# Sheet1.net
KiCad netlist of a schematic drawn in Altium Designer
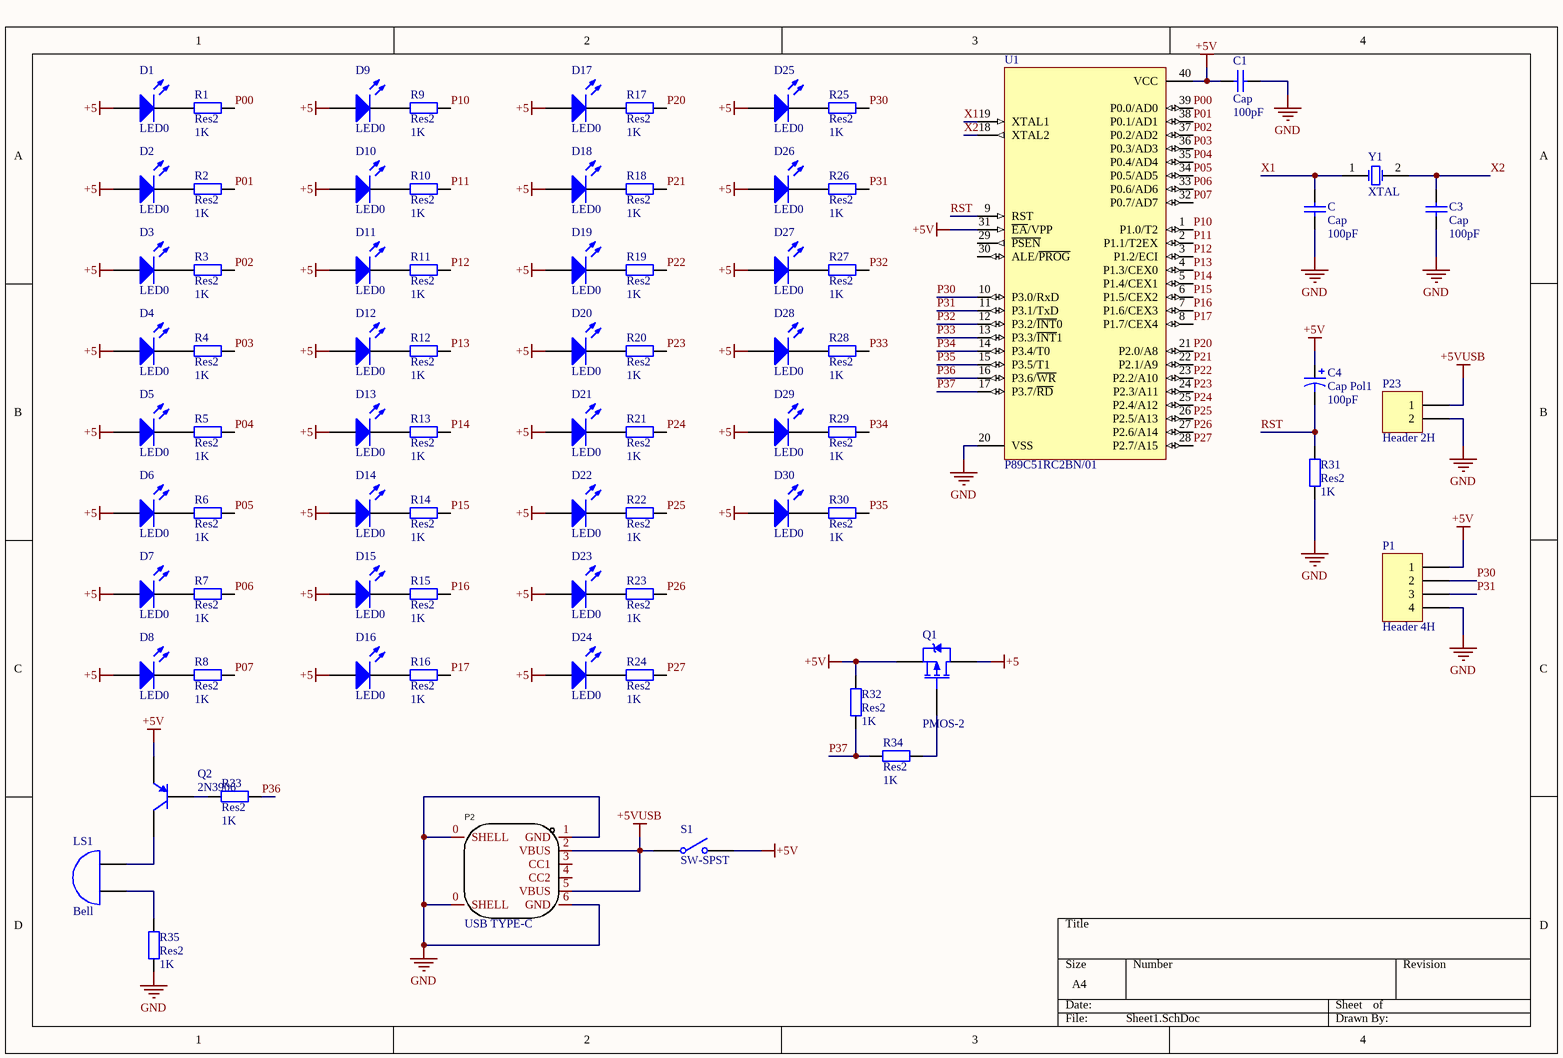
[diagram p0: Sheet1.SchDoc]

(export (version "E")
  (design (tool "Eeschema 10.0.6"))
  (components
    (comp (ref "C")
      (value "Cap")
      (footprint "C-0.1")
      (description "Capacitor")
      (fields (field (name "ALTIUM_VALUE") "100pF") (field (name "PUBLISHER") "Altium Limited"))
      (libsource (lib "Miscellaneous Devices") (part "Cap"))
    )
    (comp (ref "C1")
      (value "Cap")
      (footprint "C-0.1")
      (description "Capacitor")
      (fields (field (name "ALTIUM_VALUE") "100pF") (field (name "PUBLISHER") "Altium Limited"))
      (libsource (lib "Miscellaneous Devices") (part "Cap"))
    )
    (comp (ref "C3")
      (value "Cap")
      (footprint "C-0.1")
      (description "Capacitor")
      (fields (field (name "ALTIUM_VALUE") "100pF") (field (name "PUBLISHER") "Altium Limited"))
      (libsource (lib "Miscellaneous Devices") (part "Cap"))
    )
    (comp (ref "C4")
      (value "Cap Pol1")
      (footprint "CD-0.2T")
      (description "Polarized Capacitor (Radial)")
      (fields (field (name "ALTIUM_VALUE") "100pF") (field (name "PUBLISHER") "Altium Limited"))
      (libsource (lib "Miscellaneous Devices") (part "Cap Pol1"))
    )
    (comp (ref "D1")
      (value "LED0")
      (footprint "led5")
      (description "Typical INFRARED GaAs LED")
      (fields (field (name "PUBLISHER") "Altium Limited"))
      (libsource (lib "Miscellaneous Devices") (part "LED0"))
    )
    (comp (ref "D2")
      (value "LED0")
      (footprint "led5")
      (description "Typical INFRARED GaAs LED")
      (fields (field (name "PUBLISHER") "Altium Limited"))
      (libsource (lib "Miscellaneous Devices") (part "LED0"))
    )
    (comp (ref "D3")
      (value "LED0")
      (footprint "led5")
      (description "Typical INFRARED GaAs LED")
      (fields (field (name "PUBLISHER") "Altium Limited"))
      (libsource (lib "Miscellaneous Devices") (part "LED0"))
    )
    (comp (ref "D4")
      (value "LED0")
      (footprint "led5")
      (description "Typical INFRARED GaAs LED")
      (fields (field (name "PUBLISHER") "Altium Limited"))
      (libsource (lib "Miscellaneous Devices") (part "LED0"))
    )
    (comp (ref "D5")
      (value "LED0")
      (footprint "led5")
      (description "Typical INFRARED GaAs LED")
      (fields (field (name "PUBLISHER") "Altium Limited"))
      (libsource (lib "Miscellaneous Devices") (part "LED0"))
    )
    (comp (ref "D6")
      (value "LED0")
      (footprint "led5")
      (description "Typical INFRARED GaAs LED")
      (fields (field (name "PUBLISHER") "Altium Limited"))
      (libsource (lib "Miscellaneous Devices") (part "LED0"))
    )
    (comp (ref "D7")
      (value "LED0")
      (footprint "led5")
      (description "Typical INFRARED GaAs LED")
      (fields (field (name "PUBLISHER") "Altium Limited"))
      (libsource (lib "Miscellaneous Devices") (part "LED0"))
    )
    (comp (ref "D8")
      (value "LED0")
      (footprint "led5")
      (description "Typical INFRARED GaAs LED")
      (fields (field (name "PUBLISHER") "Altium Limited"))
      (libsource (lib "Miscellaneous Devices") (part "LED0"))
    )
    (comp (ref "D9")
      (value "LED0")
      (footprint "led5")
      (description "Typical INFRARED GaAs LED")
      (fields (field (name "PUBLISHER") "Altium Limited"))
      (libsource (lib "Miscellaneous Devices") (part "LED0"))
    )
    (comp (ref "D10")
      (value "LED0")
      (footprint "led5")
      (description "Typical INFRARED GaAs LED")
      (fields (field (name "PUBLISHER") "Altium Limited"))
      (libsource (lib "Miscellaneous Devices") (part "LED0"))
    )
    (comp (ref "D11")
      (value "LED0")
      (footprint "led5")
      (description "Typical INFRARED GaAs LED")
      (fields (field (name "PUBLISHER") "Altium Limited"))
      (libsource (lib "Miscellaneous Devices") (part "LED0"))
    )
    (comp (ref "D12")
      (value "LED0")
      (footprint "led5")
      (description "Typical INFRARED GaAs LED")
      (fields (field (name "PUBLISHER") "Altium Limited"))
      (libsource (lib "Miscellaneous Devices") (part "LED0"))
    )
    (comp (ref "D13")
      (value "LED0")
      (footprint "led5")
      (description "Typical INFRARED GaAs LED")
      (fields (field (name "PUBLISHER") "Altium Limited"))
      (libsource (lib "Miscellaneous Devices") (part "LED0"))
    )
    (comp (ref "D14")
      (value "LED0")
      (footprint "led5")
      (description "Typical INFRARED GaAs LED")
      (fields (field (name "PUBLISHER") "Altium Limited"))
      (libsource (lib "Miscellaneous Devices") (part "LED0"))
    )
    (comp (ref "D15")
      (value "LED0")
      (footprint "led5")
      (description "Typical INFRARED GaAs LED")
      (fields (field (name "PUBLISHER") "Altium Limited"))
      (libsource (lib "Miscellaneous Devices") (part "LED0"))
    )
    (comp (ref "D16")
      (value "LED0")
      (footprint "led5")
      (description "Typical INFRARED GaAs LED")
      (fields (field (name "PUBLISHER") "Altium Limited"))
      (libsource (lib "Miscellaneous Devices") (part "LED0"))
    )
    (comp (ref "D17")
      (value "LED0")
      (footprint "led5")
      (description "Typical INFRARED GaAs LED")
      (fields (field (name "PUBLISHER") "Altium Limited"))
      (libsource (lib "Miscellaneous Devices") (part "LED0"))
    )
    (comp (ref "D18")
      (value "LED0")
      (footprint "led5")
      (description "Typical INFRARED GaAs LED")
      (fields (field (name "PUBLISHER") "Altium Limited"))
      (libsource (lib "Miscellaneous Devices") (part "LED0"))
    )
    (comp (ref "D19")
      (value "LED0")
      (footprint "led5")
      (description "Typical INFRARED GaAs LED")
      (fields (field (name "PUBLISHER") "Altium Limited"))
      (libsource (lib "Miscellaneous Devices") (part "LED0"))
    )
    (comp (ref "D20")
      (value "LED0")
      (footprint "led5")
      (description "Typical INFRARED GaAs LED")
      (fields (field (name "PUBLISHER") "Altium Limited"))
      (libsource (lib "Miscellaneous Devices") (part "LED0"))
    )
    (comp (ref "D21")
      (value "LED0")
      (footprint "led5")
      (description "Typical INFRARED GaAs LED")
      (fields (field (name "PUBLISHER") "Altium Limited"))
      (libsource (lib "Miscellaneous Devices") (part "LED0"))
    )
    (comp (ref "D22")
      (value "LED0")
      (footprint "led5")
      (description "Typical INFRARED GaAs LED")
      (fields (field (name "PUBLISHER") "Altium Limited"))
      (libsource (lib "Miscellaneous Devices") (part "LED0"))
    )
    (comp (ref "D23")
      (value "LED0")
      (footprint "led5")
      (description "Typical INFRARED GaAs LED")
      (fields (field (name "PUBLISHER") "Altium Limited"))
      (libsource (lib "Miscellaneous Devices") (part "LED0"))
    )
    (comp (ref "D24")
      (value "LED0")
      (footprint "led5")
      (description "Typical INFRARED GaAs LED")
      (fields (field (name "PUBLISHER") "Altium Limited"))
      (libsource (lib "Miscellaneous Devices") (part "LED0"))
    )
    (comp (ref "D25")
      (value "LED0")
      (footprint "led5")
      (description "Typical INFRARED GaAs LED")
      (fields (field (name "PUBLISHER") "Altium Limited"))
      (libsource (lib "Miscellaneous Devices") (part "LED0"))
    )
    (comp (ref "D26")
      (value "LED0")
      (footprint "led5")
      (description "Typical INFRARED GaAs LED")
      (fields (field (name "PUBLISHER") "Altium Limited"))
      (libsource (lib "Miscellaneous Devices") (part "LED0"))
    )
    (comp (ref "D27")
      (value "LED0")
      (footprint "led5")
      (description "Typical INFRARED GaAs LED")
      (fields (field (name "PUBLISHER") "Altium Limited"))
      (libsource (lib "Miscellaneous Devices") (part "LED0"))
    )
    (comp (ref "D28")
      (value "LED0")
      (footprint "led5")
      (description "Typical INFRARED GaAs LED")
      (fields (field (name "PUBLISHER") "Altium Limited"))
      (libsource (lib "Miscellaneous Devices") (part "LED0"))
    )
    (comp (ref "D29")
      (value "LED0")
      (footprint "led5")
      (description "Typical INFRARED GaAs LED")
      (fields (field (name "PUBLISHER") "Altium Limited"))
      (libsource (lib "Miscellaneous Devices") (part "LED0"))
    )
    (comp (ref "D30")
      (value "LED0")
      (footprint "led5")
      (description "Typical INFRARED GaAs LED")
      (fields (field (name "PUBLISHER") "Altium Limited"))
      (libsource (lib "Miscellaneous Devices") (part "LED0"))
    )
    (comp (ref "LS1")
      (value "Bell")
      (footprint "PIN2")
      (description "Electrical Bell")
      (fields (field (name "PUBLISHER") "Altium Limited"))
      (libsource (lib "Miscellaneous Devices") (part "Bell"))
    )
    (comp (ref "P1")
      (value "Header 4H")
      (footprint "SIP4")
      (description "Header, 4-Pin, Right Angle")
      (fields (field (name "PUBLISHER") "Altium Limited"))
      (libsource (lib "Miscellaneous Connectors") (part "Header 4H"))
    )
    (comp (ref "P2")
      (value "USB TYPE-C")
      (footprint "USBTYPEC6")
      (fields (field (name "MANUFACTURER PART") "TYPE-C 6P CB1.6(073)"))
      (libsource (lib "EPL Scblib") (part "USB TYPE-C 6P"))
    )
    (comp (ref "P23")
      (value "Header 2H")
      (footprint "HDR1X2H")
      (description "Header, 2-Pin, Right Angle")
      (fields (field (name "PUBLISHER") "Altium Limited"))
      (libsource (lib "Miscellaneous Connectors") (part "Header 2H"))
    )
    (comp (ref "Q1")
      (value "PMOS-2")
      (footprint "sot23")
      (description "P-Channel Power MOSFET")
      (fields (field (name "PUBLISHER") "Altium Limited"))
      (libsource (lib "EPL Scblib") (part "AO3401"))
    )
    (comp (ref "Q2")
      (value "2N3906")
      (footprint "TO-92A")
      (description "PNP General Purpose Amplifier")
      (fields (field (name "PUBLISHER") "Altium Limited"))
      (libsource (lib "Miscellaneous Devices") (part "2N3906"))
    )
    (comp (ref "R1")
      (value "Res2")
      (footprint "R-0.3")
      (description "Resistor")
      (fields (field (name "ALTIUM_VALUE") "1K") (field (name "PUBLISHER") "Altium Limited"))
      (libsource (lib "Miscellaneous Devices") (part "Res2"))
    )
    (comp (ref "R2")
      (value "Res2")
      (footprint "R-0.3")
      (description "Resistor")
      (fields (field (name "ALTIUM_VALUE") "1K") (field (name "PUBLISHER") "Altium Limited"))
      (libsource (lib "Miscellaneous Devices") (part "Res2"))
    )
    (comp (ref "R3")
      (value "Res2")
      (footprint "R-0.3")
      (description "Resistor")
      (fields (field (name "ALTIUM_VALUE") "1K") (field (name "PUBLISHER") "Altium Limited"))
      (libsource (lib "Miscellaneous Devices") (part "Res2"))
    )
    (comp (ref "R4")
      (value "Res2")
      (footprint "R-0.3")
      (description "Resistor")
      (fields (field (name "ALTIUM_VALUE") "1K") (field (name "PUBLISHER") "Altium Limited"))
      (libsource (lib "Miscellaneous Devices") (part "Res2"))
    )
    (comp (ref "R5")
      (value "Res2")
      (footprint "R-0.3")
      (description "Resistor")
      (fields (field (name "ALTIUM_VALUE") "1K") (field (name "PUBLISHER") "Altium Limited"))
      (libsource (lib "Miscellaneous Devices") (part "Res2"))
    )
    (comp (ref "R6")
      (value "Res2")
      (footprint "R-0.3")
      (description "Resistor")
      (fields (field (name "ALTIUM_VALUE") "1K") (field (name "PUBLISHER") "Altium Limited"))
      (libsource (lib "Miscellaneous Devices") (part "Res2"))
    )
    (comp (ref "R7")
      (value "Res2")
      (footprint "R-0.3")
      (description "Resistor")
      (fields (field (name "ALTIUM_VALUE") "1K") (field (name "PUBLISHER") "Altium Limited"))
      (libsource (lib "Miscellaneous Devices") (part "Res2"))
    )
    (comp (ref "R8")
      (value "Res2")
      (footprint "R-0.3")
      (description "Resistor")
      (fields (field (name "ALTIUM_VALUE") "1K") (field (name "PUBLISHER") "Altium Limited"))
      (libsource (lib "Miscellaneous Devices") (part "Res2"))
    )
    (comp (ref "R9")
      (value "Res2")
      (footprint "R-0.3")
      (description "Resistor")
      (fields (field (name "ALTIUM_VALUE") "1K") (field (name "PUBLISHER") "Altium Limited"))
      (libsource (lib "Miscellaneous Devices") (part "Res2"))
    )
    (comp (ref "R10")
      (value "Res2")
      (footprint "R-0.3")
      (description "Resistor")
      (fields (field (name "ALTIUM_VALUE") "1K") (field (name "PUBLISHER") "Altium Limited"))
      (libsource (lib "Miscellaneous Devices") (part "Res2"))
    )
    (comp (ref "R11")
      (value "Res2")
      (footprint "R-0.3")
      (description "Resistor")
      (fields (field (name "ALTIUM_VALUE") "1K") (field (name "PUBLISHER") "Altium Limited"))
      (libsource (lib "Miscellaneous Devices") (part "Res2"))
    )
    (comp (ref "R12")
      (value "Res2")
      (footprint "R-0.3")
      (description "Resistor")
      (fields (field (name "ALTIUM_VALUE") "1K") (field (name "PUBLISHER") "Altium Limited"))
      (libsource (lib "Miscellaneous Devices") (part "Res2"))
    )
    (comp (ref "R13")
      (value "Res2")
      (footprint "R-0.3")
      (description "Resistor")
      (fields (field (name "ALTIUM_VALUE") "1K") (field (name "PUBLISHER") "Altium Limited"))
      (libsource (lib "Miscellaneous Devices") (part "Res2"))
    )
    (comp (ref "R14")
      (value "Res2")
      (footprint "R-0.3")
      (description "Resistor")
      (fields (field (name "ALTIUM_VALUE") "1K") (field (name "PUBLISHER") "Altium Limited"))
      (libsource (lib "Miscellaneous Devices") (part "Res2"))
    )
    (comp (ref "R15")
      (value "Res2")
      (footprint "R-0.3")
      (description "Resistor")
      (fields (field (name "ALTIUM_VALUE") "1K") (field (name "PUBLISHER") "Altium Limited"))
      (libsource (lib "Miscellaneous Devices") (part "Res2"))
    )
    (comp (ref "R16")
      (value "Res2")
      (footprint "R-0.3")
      (description "Resistor")
      (fields (field (name "ALTIUM_VALUE") "1K") (field (name "PUBLISHER") "Altium Limited"))
      (libsource (lib "Miscellaneous Devices") (part "Res2"))
    )
    (comp (ref "R17")
      (value "Res2")
      (footprint "R-0.3")
      (description "Resistor")
      (fields (field (name "ALTIUM_VALUE") "1K") (field (name "PUBLISHER") "Altium Limited"))
      (libsource (lib "Miscellaneous Devices") (part "Res2"))
    )
    (comp (ref "R18")
      (value "Res2")
      (footprint "R-0.3")
      (description "Resistor")
      (fields (field (name "ALTIUM_VALUE") "1K") (field (name "PUBLISHER") "Altium Limited"))
      (libsource (lib "Miscellaneous Devices") (part "Res2"))
    )
    (comp (ref "R19")
      (value "Res2")
      (footprint "R-0.3")
      (description "Resistor")
      (fields (field (name "ALTIUM_VALUE") "1K") (field (name "PUBLISHER") "Altium Limited"))
      (libsource (lib "Miscellaneous Devices") (part "Res2"))
    )
    (comp (ref "R20")
      (value "Res2")
      (footprint "R-0.3")
      (description "Resistor")
      (fields (field (name "ALTIUM_VALUE") "1K") (field (name "PUBLISHER") "Altium Limited"))
      (libsource (lib "Miscellaneous Devices") (part "Res2"))
    )
    (comp (ref "R21")
      (value "Res2")
      (footprint "R-0.3")
      (description "Resistor")
      (fields (field (name "ALTIUM_VALUE") "1K") (field (name "PUBLISHER") "Altium Limited"))
      (libsource (lib "Miscellaneous Devices") (part "Res2"))
    )
    (comp (ref "R22")
      (value "Res2")
      (footprint "R-0.3")
      (description "Resistor")
      (fields (field (name "ALTIUM_VALUE") "1K") (field (name "PUBLISHER") "Altium Limited"))
      (libsource (lib "Miscellaneous Devices") (part "Res2"))
    )
    (comp (ref "R23")
      (value "Res2")
      (footprint "R-0.3")
      (description "Resistor")
      (fields (field (name "ALTIUM_VALUE") "1K") (field (name "PUBLISHER") "Altium Limited"))
      (libsource (lib "Miscellaneous Devices") (part "Res2"))
    )
    (comp (ref "R24")
      (value "Res2")
      (footprint "R-0.3")
      (description "Resistor")
      (fields (field (name "ALTIUM_VALUE") "1K") (field (name "PUBLISHER") "Altium Limited"))
      (libsource (lib "Miscellaneous Devices") (part "Res2"))
    )
    (comp (ref "R25")
      (value "Res2")
      (footprint "R-0.3")
      (description "Resistor")
      (fields (field (name "ALTIUM_VALUE") "1K") (field (name "PUBLISHER") "Altium Limited"))
      (libsource (lib "Miscellaneous Devices") (part "Res2"))
    )
    (comp (ref "R26")
      (value "Res2")
      (footprint "R-0.3")
      (description "Resistor")
      (fields (field (name "ALTIUM_VALUE") "1K") (field (name "PUBLISHER") "Altium Limited"))
      (libsource (lib "Miscellaneous Devices") (part "Res2"))
    )
    (comp (ref "R27")
      (value "Res2")
      (footprint "R-0.3")
      (description "Resistor")
      (fields (field (name "ALTIUM_VALUE") "1K") (field (name "PUBLISHER") "Altium Limited"))
      (libsource (lib "Miscellaneous Devices") (part "Res2"))
    )
    (comp (ref "R28")
      (value "Res2")
      (footprint "R-0.3")
      (description "Resistor")
      (fields (field (name "ALTIUM_VALUE") "1K") (field (name "PUBLISHER") "Altium Limited"))
      (libsource (lib "Miscellaneous Devices") (part "Res2"))
    )
    (comp (ref "R29")
      (value "Res2")
      (footprint "R-0.3")
      (description "Resistor")
      (fields (field (name "ALTIUM_VALUE") "1K") (field (name "PUBLISHER") "Altium Limited"))
      (libsource (lib "Miscellaneous Devices") (part "Res2"))
    )
    (comp (ref "R30")
      (value "Res2")
      (footprint "R-0.3")
      (description "Resistor")
      (fields (field (name "ALTIUM_VALUE") "1K") (field (name "PUBLISHER") "Altium Limited"))
      (libsource (lib "Miscellaneous Devices") (part "Res2"))
    )
    (comp (ref "R31")
      (value "Res2")
      (footprint "R-0.3")
      (description "Resistor")
      (fields (field (name "ALTIUM_VALUE") "1K") (field (name "PUBLISHER") "Altium Limited"))
      (libsource (lib "") (part "Res2_1"))
    )
    (comp (ref "R32")
      (value "Res2")
      (footprint "R-0.3")
      (description "Resistor")
      (fields (field (name "ALTIUM_VALUE") "1K") (field (name "PUBLISHER") "Altium Limited"))
      (libsource (lib "") (part "Res2_1"))
    )
    (comp (ref "R33")
      (value "Res2")
      (footprint "R-0.3")
      (description "Resistor")
      (fields (field (name "ALTIUM_VALUE") "1K") (field (name "PUBLISHER") "Altium Limited"))
      (libsource (lib "") (part "Res2_2"))
    )
    (comp (ref "R34")
      (value "Res2")
      (footprint "R-0.3")
      (description "Resistor")
      (fields (field (name "ALTIUM_VALUE") "1K") (field (name "PUBLISHER") "Altium Limited"))
      (libsource (lib "") (part "Res2_2"))
    )
    (comp (ref "R35")
      (value "Res2")
      (footprint "R-0.3")
      (description "Resistor")
      (fields (field (name "ALTIUM_VALUE") "1K") (field (name "PUBLISHER") "Altium Limited"))
      (libsource (lib "") (part "Res2_1"))
    )
    (comp (ref "S1")
      (value "SW-SPST")
      (footprint "onoff")
      (description "Single-Pole, Single-Throw Switch")
      (fields (field (name "PUBLISHER") "Altium Limited"))
      (libsource (lib "Miscellaneous Devices") (part "SW-SPST"))
    )
    (comp (ref "U1")
      (value "P89C51RC2BN/01")
      (footprint "DIP40")
      (description "80C51 8-Bit Flash Microcontroller Family, 32 kB ISP/IAP Flash with 512 B RAM.")
      (fields (field (name "PUBLISHER") "Altium Limited"))
      (libsource (lib "Philips Microcontroller 8-Bit") (part "P89C51RC2BN/01"))
    )
    (comp (ref "Y1")
      (value "XTAL")
      (footprint "jz")
      (description "Crystal Oscillator")
      (fields (field (name "PUBLISHER") "Altium Limited"))
      (libsource (lib "Miscellaneous Devices") (part "XTAL"))
    )
  )
  (nets
    (net (code "1") (name "+5") (class "Default")
      (node (ref "D1") (pin "1") (pinfunction "A_1") (pintype "passive"))
      (node (ref "D10") (pin "1") (pinfunction "A_1") (pintype "passive"))
      (node (ref "D11") (pin "1") (pinfunction "A_1") (pintype "passive"))
      (node (ref "D12") (pin "1") (pinfunction "A_1") (pintype "passive"))
      (node (ref "D13") (pin "1") (pinfunction "A_1") (pintype "passive"))
      (node (ref "D14") (pin "1") (pinfunction "A_1") (pintype "passive"))
      (node (ref "D15") (pin "1") (pinfunction "A_1") (pintype "passive"))
      (node (ref "D16") (pin "1") (pinfunction "A_1") (pintype "passive"))
      (node (ref "D17") (pin "1") (pinfunction "A_1") (pintype "passive"))
      (node (ref "D18") (pin "1") (pinfunction "A_1") (pintype "passive"))
      (node (ref "D19") (pin "1") (pinfunction "A_1") (pintype "passive"))
      (node (ref "D2") (pin "1") (pinfunction "A_1") (pintype "passive"))
      (node (ref "D20") (pin "1") (pinfunction "A_1") (pintype "passive"))
      (node (ref "D21") (pin "1") (pinfunction "A_1") (pintype "passive"))
      (node (ref "D22") (pin "1") (pinfunction "A_1") (pintype "passive"))
      (node (ref "D23") (pin "1") (pinfunction "A_1") (pintype "passive"))
      (node (ref "D24") (pin "1") (pinfunction "A_1") (pintype "passive"))
      (node (ref "D25") (pin "1") (pinfunction "A_1") (pintype "passive"))
      (node (ref "D26") (pin "1") (pinfunction "A_1") (pintype "passive"))
      (node (ref "D27") (pin "1") (pinfunction "A_1") (pintype "passive"))
      (node (ref "D28") (pin "1") (pinfunction "A_1") (pintype "passive"))
      (node (ref "D29") (pin "1") (pinfunction "A_1") (pintype "passive"))
      (node (ref "D3") (pin "1") (pinfunction "A_1") (pintype "passive"))
      (node (ref "D30") (pin "1") (pinfunction "A_1") (pintype "passive"))
      (node (ref "D4") (pin "1") (pinfunction "A_1") (pintype "passive"))
      (node (ref "D5") (pin "1") (pinfunction "A_1") (pintype "passive"))
      (node (ref "D6") (pin "1") (pinfunction "A_1") (pintype "passive"))
      (node (ref "D7") (pin "1") (pinfunction "A_1") (pintype "passive"))
      (node (ref "D8") (pin "1") (pinfunction "A_1") (pintype "passive"))
      (node (ref "D9") (pin "1") (pinfunction "A_1") (pintype "passive"))
      (node (ref "Q1") (pin "3") (pinfunction "D_3") (pintype "passive"))
    )
    (net (code "2") (name "+5V") (class "Default")
      (node (ref "C1") (pin "1") (pinfunction "1_1") (pintype "passive"))
      (node (ref "C4") (pin "1") (pinfunction "1_1") (pintype "passive"))
      (node (ref "P1") (pin "1") (pinfunction "1_1") (pintype "passive"))
      (node (ref "Q1") (pin "2") (pinfunction "S_2") (pintype "passive"))
      (node (ref "Q2") (pin "1") (pinfunction "E_1") (pintype "passive"))
      (node (ref "R32") (pin "2") (pinfunction "2_2") (pintype "passive"))
      (node (ref "S1") (pin "2") (pinfunction "NO_2") (pintype "passive"))
      (node (ref "U1") (pin "31") (pinfunction "~{EA}/VPP_31") (pintype "input"))
      (node (ref "U1") (pin "40") (pinfunction "VCC_40") (pintype "power_in"))
    )
    (net (code "3") (name "+5VUSB") (class "Default")
      (node (ref "P2") (pin "2") (pinfunction "VBUS_2") (pintype "passive"))
      (node (ref "P2") (pin "5") (pinfunction "VBUS_5") (pintype "passive"))
      (node (ref "P23") (pin "1") (pinfunction "1_1") (pintype "passive"))
      (node (ref "S1") (pin "1") (pinfunction "COMMON_1") (pintype "passive"))
    )
    (net (code "4") (name "/P00") (class "Default")
      (node (ref "R1") (pin "2") (pinfunction "2_2") (pintype "passive"))
      (node (ref "U1") (pin "39") (pinfunction "P0.0/AD0_39") (pintype "bidirectional"))
    )
    (net (code "5") (name "/P01") (class "Default")
      (node (ref "R2") (pin "2") (pinfunction "2_2") (pintype "passive"))
      (node (ref "U1") (pin "38") (pinfunction "P0.1/AD1_38") (pintype "bidirectional"))
    )
    (net (code "6") (name "/P02") (class "Default")
      (node (ref "R3") (pin "2") (pinfunction "2_2") (pintype "passive"))
      (node (ref "U1") (pin "37") (pinfunction "P0.2/AD2_37") (pintype "bidirectional"))
    )
    (net (code "7") (name "/P03") (class "Default")
      (node (ref "R4") (pin "2") (pinfunction "2_2") (pintype "passive"))
      (node (ref "U1") (pin "36") (pinfunction "P0.3/AD3_36") (pintype "bidirectional"))
    )
    (net (code "8") (name "/P04") (class "Default")
      (node (ref "R5") (pin "2") (pinfunction "2_2") (pintype "passive"))
      (node (ref "U1") (pin "35") (pinfunction "P0.4/AD4_35") (pintype "bidirectional"))
    )
    (net (code "9") (name "/P05") (class "Default")
      (node (ref "R6") (pin "2") (pinfunction "2_2") (pintype "passive"))
      (node (ref "U1") (pin "34") (pinfunction "P0.5/AD5_34") (pintype "bidirectional"))
    )
    (net (code "10") (name "/P06") (class "Default")
      (node (ref "R7") (pin "2") (pinfunction "2_2") (pintype "passive"))
      (node (ref "U1") (pin "33") (pinfunction "P0.6/AD6_33") (pintype "bidirectional"))
    )
    (net (code "11") (name "/P07") (class "Default")
      (node (ref "R8") (pin "2") (pinfunction "2_2") (pintype "passive"))
      (node (ref "U1") (pin "32") (pinfunction "P0.7/AD7_32") (pintype "bidirectional"))
    )
    (net (code "12") (name "/P10") (class "Default")
      (node (ref "R9") (pin "2") (pinfunction "2_2") (pintype "passive"))
      (node (ref "U1") (pin "1") (pinfunction "P1.0/T2_1") (pintype "bidirectional"))
    )
    (net (code "13") (name "/P11") (class "Default")
      (node (ref "R10") (pin "2") (pinfunction "2_2") (pintype "passive"))
      (node (ref "U1") (pin "2") (pinfunction "P1.1/T2EX_2") (pintype "bidirectional"))
    )
    (net (code "14") (name "/P12") (class "Default")
      (node (ref "R11") (pin "2") (pinfunction "2_2") (pintype "passive"))
      (node (ref "U1") (pin "3") (pinfunction "P1.2/ECI_3") (pintype "bidirectional"))
    )
    (net (code "15") (name "/P13") (class "Default")
      (node (ref "R12") (pin "2") (pinfunction "2_2") (pintype "passive"))
      (node (ref "U1") (pin "4") (pinfunction "P1.3/CEX0_4") (pintype "bidirectional"))
    )
    (net (code "16") (name "/P14") (class "Default")
      (node (ref "R13") (pin "2") (pinfunction "2_2") (pintype "passive"))
      (node (ref "U1") (pin "5") (pinfunction "P1.4/CEX1_5") (pintype "bidirectional"))
    )
    (net (code "17") (name "/P15") (class "Default")
      (node (ref "R14") (pin "2") (pinfunction "2_2") (pintype "passive"))
      (node (ref "U1") (pin "6") (pinfunction "P1.5/CEX2_6") (pintype "bidirectional"))
    )
    (net (code "18") (name "/P16") (class "Default")
      (node (ref "R15") (pin "2") (pinfunction "2_2") (pintype "passive"))
      (node (ref "U1") (pin "7") (pinfunction "P1.6/CEX3_7") (pintype "bidirectional"))
    )
    (net (code "19") (name "/P17") (class "Default")
      (node (ref "R16") (pin "2") (pinfunction "2_2") (pintype "passive"))
      (node (ref "U1") (pin "8") (pinfunction "P1.7/CEX4_8") (pintype "bidirectional"))
    )
    (net (code "20") (name "/P20") (class "Default")
      (node (ref "R17") (pin "2") (pinfunction "2_2") (pintype "passive"))
      (node (ref "U1") (pin "21") (pinfunction "P2.0/A8_21") (pintype "bidirectional"))
    )
    (net (code "21") (name "/P21") (class "Default")
      (node (ref "R18") (pin "2") (pinfunction "2_2") (pintype "passive"))
      (node (ref "U1") (pin "22") (pinfunction "P2.1/A9_22") (pintype "bidirectional"))
    )
    (net (code "22") (name "/P22") (class "Default")
      (node (ref "R19") (pin "2") (pinfunction "2_2") (pintype "passive"))
      (node (ref "U1") (pin "23") (pinfunction "P2.2/A10_23") (pintype "bidirectional"))
    )
    (net (code "23") (name "/P23") (class "Default")
      (node (ref "R20") (pin "2") (pinfunction "2_2") (pintype "passive"))
      (node (ref "U1") (pin "24") (pinfunction "P2.3/A11_24") (pintype "bidirectional"))
    )
    (net (code "24") (name "/P24") (class "Default")
      (node (ref "R21") (pin "2") (pinfunction "2_2") (pintype "passive"))
      (node (ref "U1") (pin "25") (pinfunction "P2.4/A12_25") (pintype "bidirectional"))
    )
    (net (code "25") (name "/P25") (class "Default")
      (node (ref "R22") (pin "2") (pinfunction "2_2") (pintype "passive"))
      (node (ref "U1") (pin "26") (pinfunction "P2.5/A13_26") (pintype "bidirectional"))
    )
    (net (code "26") (name "/P26") (class "Default")
      (node (ref "R23") (pin "2") (pinfunction "2_2") (pintype "passive"))
      (node (ref "U1") (pin "27") (pinfunction "P2.6/A14_27") (pintype "bidirectional"))
    )
    (net (code "27") (name "/P27") (class "Default")
      (node (ref "R24") (pin "2") (pinfunction "2_2") (pintype "passive"))
      (node (ref "U1") (pin "28") (pinfunction "P2.7/A15_28") (pintype "bidirectional"))
    )
    (net (code "28") (name "/P30") (class "Default")
      (node (ref "P1") (pin "2") (pinfunction "2_2") (pintype "passive"))
      (node (ref "R25") (pin "2") (pinfunction "2_2") (pintype "passive"))
      (node (ref "U1") (pin "10") (pinfunction "P3.0/RxD_10") (pintype "bidirectional"))
    )
    (net (code "29") (name "/P31") (class "Default")
      (node (ref "P1") (pin "3") (pinfunction "3_3") (pintype "passive"))
      (node (ref "R26") (pin "2") (pinfunction "2_2") (pintype "passive"))
      (node (ref "U1") (pin "11") (pinfunction "P3.1/TxD_11") (pintype "bidirectional"))
    )
    (net (code "30") (name "/P32") (class "Default")
      (node (ref "R27") (pin "2") (pinfunction "2_2") (pintype "passive"))
      (node (ref "U1") (pin "12") (pinfunction "P3.2/~{INT}0_12") (pintype "bidirectional"))
    )
    (net (code "31") (name "/P33") (class "Default")
      (node (ref "R28") (pin "2") (pinfunction "2_2") (pintype "passive"))
      (node (ref "U1") (pin "13") (pinfunction "P3.3/~{INT}1_13") (pintype "bidirectional"))
    )
    (net (code "32") (name "/P34") (class "Default")
      (node (ref "R29") (pin "2") (pinfunction "2_2") (pintype "passive"))
      (node (ref "U1") (pin "14") (pinfunction "P3.4/T0_14") (pintype "bidirectional"))
    )
    (net (code "33") (name "/P35") (class "Default")
      (node (ref "R30") (pin "2") (pinfunction "2_2") (pintype "passive"))
      (node (ref "U1") (pin "15") (pinfunction "P3.5/T1_15") (pintype "bidirectional"))
    )
    (net (code "34") (name "/P36") (class "Default")
      (node (ref "R33") (pin "1") (pinfunction "1_1") (pintype "passive"))
      (node (ref "U1") (pin "16") (pinfunction "P3.6/~{WR}_16") (pintype "bidirectional"))
    )
    (net (code "35") (name "/P37") (class "Default")
      (node (ref "R32") (pin "1") (pinfunction "1_1") (pintype "passive"))
      (node (ref "R34") (pin "2") (pinfunction "2_2") (pintype "passive"))
      (node (ref "U1") (pin "17") (pinfunction "P3.7/~{RD}_17") (pintype "bidirectional"))
    )
    (net (code "36") (name "/RST") (class "Default")
      (node (ref "C4") (pin "2") (pinfunction "2_2") (pintype "passive"))
      (node (ref "R31") (pin "2") (pinfunction "2_2") (pintype "passive"))
      (node (ref "U1") (pin "9") (pinfunction "RST_9") (pintype "input"))
    )
    (net (code "37") (name "/X1") (class "Default")
      (node (ref "C") (pin "2") (pinfunction "2_2") (pintype "passive"))
      (node (ref "U1") (pin "19") (pinfunction "XTAL1_19") (pintype "input"))
      (node (ref "Y1") (pin "1") (pinfunction "OSC1_1") (pintype "passive"))
    )
    (net (code "38") (name "/X2") (class "Default")
      (node (ref "C3") (pin "2") (pinfunction "2_2") (pintype "passive"))
      (node (ref "U1") (pin "18") (pinfunction "XTAL2_18") (pintype "output"))
      (node (ref "Y1") (pin "2") (pinfunction "OSC2_2") (pintype "passive"))
    )
    (net (code "39") (name "GND") (class "Default")
      (node (ref "C") (pin "1") (pinfunction "1_1") (pintype "passive"))
      (node (ref "C1") (pin "2") (pinfunction "2_2") (pintype "passive"))
      (node (ref "C3") (pin "1") (pinfunction "1_1") (pintype "passive"))
      (node (ref "P1") (pin "4") (pinfunction "4_4") (pintype "passive"))
      (node (ref "P2") (pin "0") (pinfunction "SHELL_0") (pintype "passive"))
      (node (ref "P2") (pin "1") (pinfunction "GND_1") (pintype "passive"))
      (node (ref "P2") (pin "6") (pinfunction "GND_6") (pintype "passive"))
      (node (ref "P23") (pin "2") (pinfunction "2_2") (pintype "passive"))
      (node (ref "R31") (pin "1") (pinfunction "1_1") (pintype "passive"))
      (node (ref "R35") (pin "1") (pinfunction "1_1") (pintype "passive"))
      (node (ref "U1") (pin "20") (pinfunction "VSS_20") (pintype "power_in"))
    )
    (net (code "40") (name "Net-(D1-K)") (class "Default")
      (node (ref "D1") (pin "2") (pinfunction "K_2") (pintype "passive"))
      (node (ref "R1") (pin "1") (pinfunction "1_1") (pintype "passive"))
    )
    (net (code "41") (name "Net-(D2-K)") (class "Default")
      (node (ref "D2") (pin "2") (pinfunction "K_2") (pintype "passive"))
      (node (ref "R2") (pin "1") (pinfunction "1_1") (pintype "passive"))
    )
    (net (code "42") (name "Net-(D3-K)") (class "Default")
      (node (ref "D3") (pin "2") (pinfunction "K_2") (pintype "passive"))
      (node (ref "R3") (pin "1") (pinfunction "1_1") (pintype "passive"))
    )
    (net (code "43") (name "Net-(D4-K)") (class "Default")
      (node (ref "D4") (pin "2") (pinfunction "K_2") (pintype "passive"))
      (node (ref "R4") (pin "1") (pinfunction "1_1") (pintype "passive"))
    )
    (net (code "44") (name "Net-(D5-K)") (class "Default")
      (node (ref "D5") (pin "2") (pinfunction "K_2") (pintype "passive"))
      (node (ref "R5") (pin "1") (pinfunction "1_1") (pintype "passive"))
    )
    (net (code "45") (name "Net-(D6-K)") (class "Default")
      (node (ref "D6") (pin "2") (pinfunction "K_2") (pintype "passive"))
      (node (ref "R6") (pin "1") (pinfunction "1_1") (pintype "passive"))
    )
    (net (code "46") (name "Net-(D7-K)") (class "Default")
      (node (ref "D7") (pin "2") (pinfunction "K_2") (pintype "passive"))
      (node (ref "R7") (pin "1") (pinfunction "1_1") (pintype "passive"))
    )
    (net (code "47") (name "Net-(D8-K)") (class "Default")
      (node (ref "D8") (pin "2") (pinfunction "K_2") (pintype "passive"))
      (node (ref "R8") (pin "1") (pinfunction "1_1") (pintype "passive"))
    )
    (net (code "48") (name "Net-(D9-K)") (class "Default")
      (node (ref "D9") (pin "2") (pinfunction "K_2") (pintype "passive"))
      (node (ref "R9") (pin "1") (pinfunction "1_1") (pintype "passive"))
    )
    (net (code "49") (name "Net-(D10-K)") (class "Default")
      (node (ref "D10") (pin "2") (pinfunction "K_2") (pintype "passive"))
      (node (ref "R10") (pin "1") (pinfunction "1_1") (pintype "passive"))
    )
    (net (code "50") (name "Net-(D11-K)") (class "Default")
      (node (ref "D11") (pin "2") (pinfunction "K_2") (pintype "passive"))
      (node (ref "R11") (pin "1") (pinfunction "1_1") (pintype "passive"))
    )
    (net (code "51") (name "Net-(D12-K)") (class "Default")
      (node (ref "D12") (pin "2") (pinfunction "K_2") (pintype "passive"))
      (node (ref "R12") (pin "1") (pinfunction "1_1") (pintype "passive"))
    )
    (net (code "52") (name "Net-(D13-K)") (class "Default")
      (node (ref "D13") (pin "2") (pinfunction "K_2") (pintype "passive"))
      (node (ref "R13") (pin "1") (pinfunction "1_1") (pintype "passive"))
    )
    (net (code "53") (name "Net-(D14-K)") (class "Default")
      (node (ref "D14") (pin "2") (pinfunction "K_2") (pintype "passive"))
      (node (ref "R14") (pin "1") (pinfunction "1_1") (pintype "passive"))
    )
    (net (code "54") (name "Net-(D15-K)") (class "Default")
      (node (ref "D15") (pin "2") (pinfunction "K_2") (pintype "passive"))
      (node (ref "R15") (pin "1") (pinfunction "1_1") (pintype "passive"))
    )
    (net (code "55") (name "Net-(D16-K)") (class "Default")
      (node (ref "D16") (pin "2") (pinfunction "K_2") (pintype "passive"))
      (node (ref "R16") (pin "1") (pinfunction "1_1") (pintype "passive"))
    )
    (net (code "56") (name "Net-(D17-K)") (class "Default")
      (node (ref "D17") (pin "2") (pinfunction "K_2") (pintype "passive"))
      (node (ref "R17") (pin "1") (pinfunction "1_1") (pintype "passive"))
    )
    (net (code "57") (name "Net-(D18-K)") (class "Default")
      (node (ref "D18") (pin "2") (pinfunction "K_2") (pintype "passive"))
      (node (ref "R18") (pin "1") (pinfunction "1_1") (pintype "passive"))
    )
    (net (code "58") (name "Net-(D19-K)") (class "Default")
      (node (ref "D19") (pin "2") (pinfunction "K_2") (pintype "passive"))
      (node (ref "R19") (pin "1") (pinfunction "1_1") (pintype "passive"))
    )
    (net (code "59") (name "Net-(D20-K)") (class "Default")
      (node (ref "D20") (pin "2") (pinfunction "K_2") (pintype "passive"))
      (node (ref "R20") (pin "1") (pinfunction "1_1") (pintype "passive"))
    )
    (net (code "60") (name "Net-(D21-K)") (class "Default")
      (node (ref "D21") (pin "2") (pinfunction "K_2") (pintype "passive"))
      (node (ref "R21") (pin "1") (pinfunction "1_1") (pintype "passive"))
    )
    (net (code "61") (name "Net-(D22-K)") (class "Default")
      (node (ref "D22") (pin "2") (pinfunction "K_2") (pintype "passive"))
      (node (ref "R22") (pin "1") (pinfunction "1_1") (pintype "passive"))
    )
    (net (code "62") (name "Net-(D23-K)") (class "Default")
      (node (ref "D23") (pin "2") (pinfunction "K_2") (pintype "passive"))
      (node (ref "R23") (pin "1") (pinfunction "1_1") (pintype "passive"))
    )
    (net (code "63") (name "Net-(D24-K)") (class "Default")
      (node (ref "D24") (pin "2") (pinfunction "K_2") (pintype "passive"))
      (node (ref "R24") (pin "1") (pinfunction "1_1") (pintype "passive"))
    )
    (net (code "64") (name "Net-(D25-K)") (class "Default")
      (node (ref "D25") (pin "2") (pinfunction "K_2") (pintype "passive"))
      (node (ref "R25") (pin "1") (pinfunction "1_1") (pintype "passive"))
    )
    (net (code "65") (name "Net-(D26-K)") (class "Default")
      (node (ref "D26") (pin "2") (pinfunction "K_2") (pintype "passive"))
      (node (ref "R26") (pin "1") (pinfunction "1_1") (pintype "passive"))
    )
    (net (code "66") (name "Net-(D27-K)") (class "Default")
      (node (ref "D27") (pin "2") (pinfunction "K_2") (pintype "passive"))
      (node (ref "R27") (pin "1") (pinfunction "1_1") (pintype "passive"))
    )
    (net (code "67") (name "Net-(D28-K)") (class "Default")
      (node (ref "D28") (pin "2") (pinfunction "K_2") (pintype "passive"))
      (node (ref "R28") (pin "1") (pinfunction "1_1") (pintype "passive"))
    )
    (net (code "68") (name "Net-(D29-K)") (class "Default")
      (node (ref "D29") (pin "2") (pinfunction "K_2") (pintype "passive"))
      (node (ref "R29") (pin "1") (pinfunction "1_1") (pintype "passive"))
    )
    (net (code "69") (name "Net-(D30-K)") (class "Default")
      (node (ref "D30") (pin "2") (pinfunction "K_2") (pintype "passive"))
      (node (ref "R30") (pin "1") (pinfunction "1_1") (pintype "passive"))
    )
    (net (code "70") (name "Net-(LS1-A)") (class "Default")
      (node (ref "LS1") (pin "1") (pinfunction "A_1") (pintype "passive"))
      (node (ref "R35") (pin "2") (pinfunction "2_2") (pintype "passive"))
    )
    (net (code "71") (name "Net-(LS1-B)") (class "Default")
      (node (ref "LS1") (pin "2") (pinfunction "B_2") (pintype "passive"))
      (node (ref "Q2") (pin "3") (pinfunction "C_3") (pintype "passive"))
    )
    (net (code "72") (name "Net-(Q1-G)") (class "Default")
      (node (ref "Q1") (pin "1") (pinfunction "G_1") (pintype "passive"))
      (node (ref "R34") (pin "1") (pinfunction "1_1") (pintype "passive"))
    )
    (net (code "73") (name "Net-(Q2-B)") (class "Default")
      (node (ref "Q2") (pin "2") (pinfunction "B_2") (pintype "passive"))
      (node (ref "R33") (pin "2") (pinfunction "2_2") (pintype "passive"))
    )
    (net (code "74") (name "unconnected-(P2-CC1-Pad3)") (class "Default")
      (node (ref "P2") (pin "3") (pinfunction "CC1_3") (pintype "passive"))
    )
    (net (code "75") (name "unconnected-(P2-CC2-Pad4)") (class "Default")
      (node (ref "P2") (pin "4") (pinfunction "CC2_4") (pintype "passive"))
    )
    (net (code "76") (name "unconnected-(U1-ALE{slash}~{PROG}-Pad30)") (class "Default")
      (node (ref "U1") (pin "30") (pinfunction "ALE/~{PROG}_30") (pintype "bidirectional"))
    )
    (net (code "77") (name "unconnected-(U1-~{PSEN}-Pad29)") (class "Default")
      (node (ref "U1") (pin "29") (pinfunction "~{PSEN}_29") (pintype "output"))
    )
  )
)
